# EuclideanSequencer.net
KiCad netlist of a schematic drawn in EAGLE
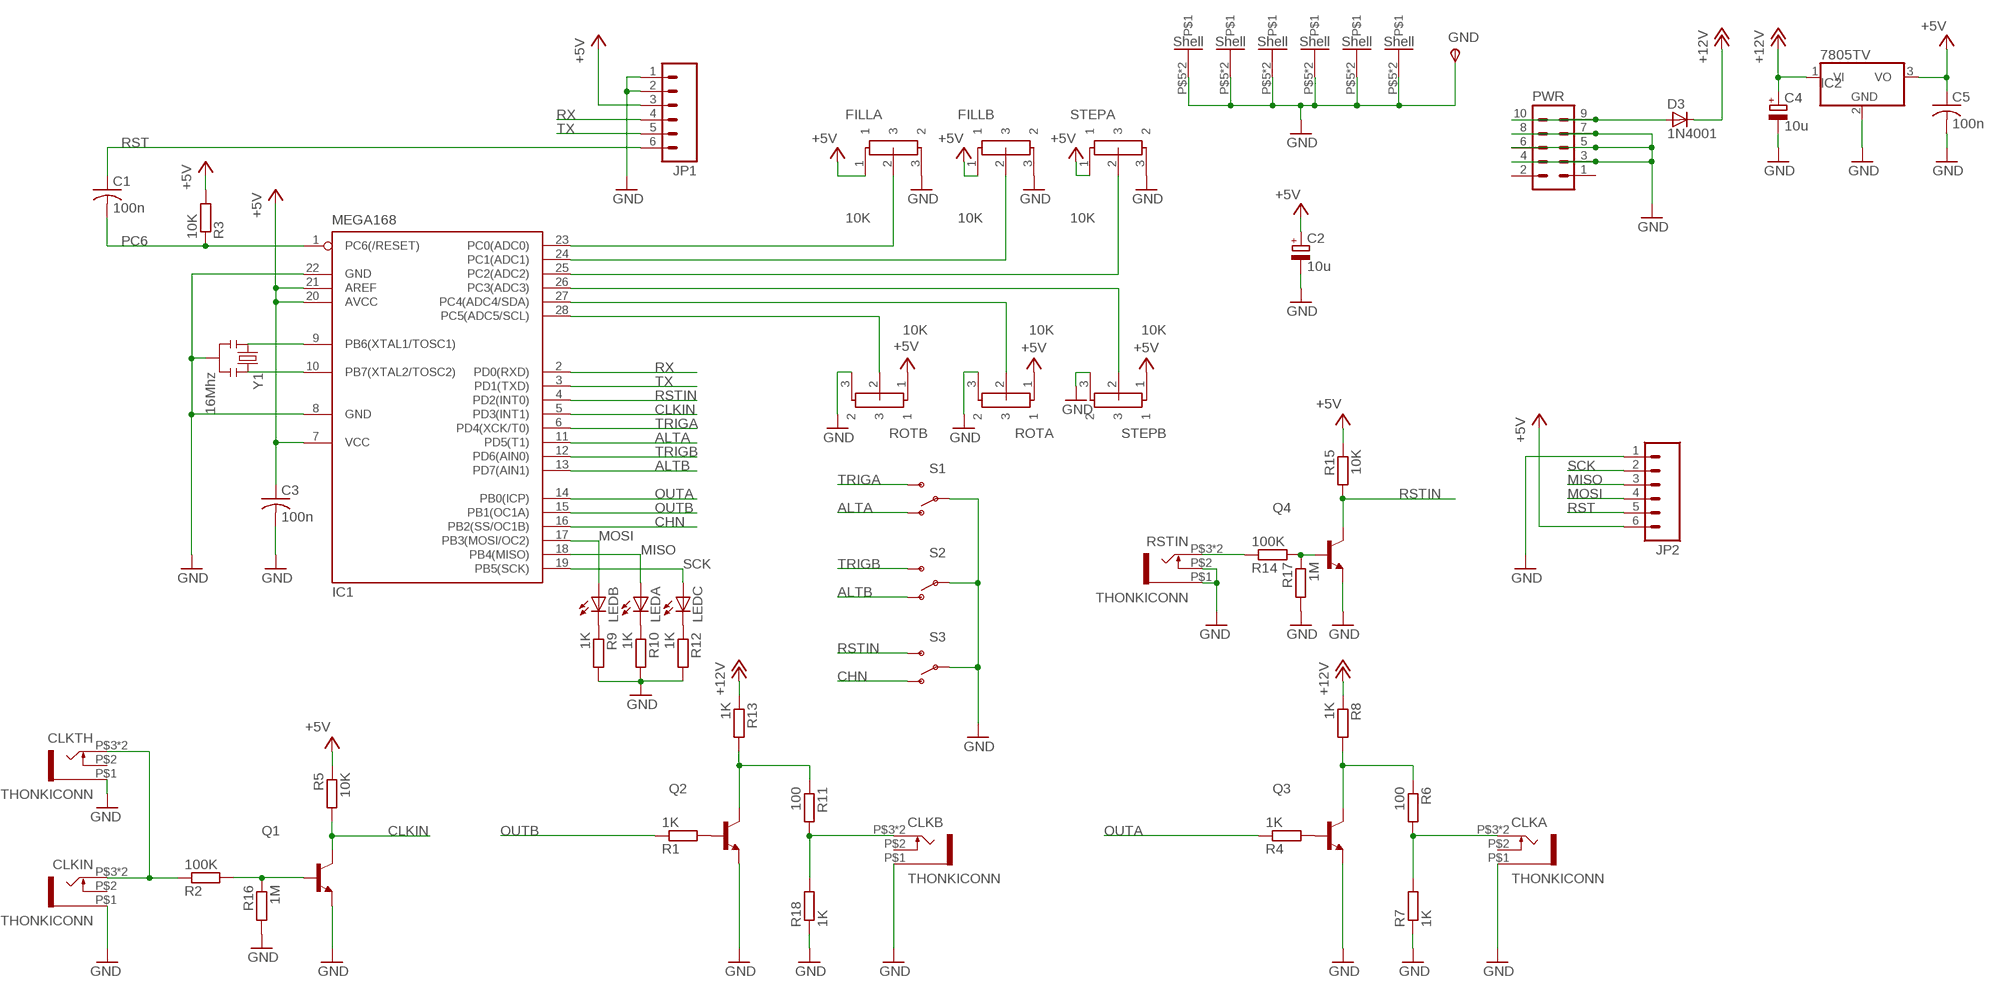
[diagram p0: schematic, sheet 1]

(export (version "E")
  (design (tool "Eeschema 10.0.6"))
  (components
    (comp (ref "C1")
      (value "100n")
      (footprint "eagle-import:C050-024X044")
      (libsource (lib "eagle-import") (part "C-US050-024X044"))
    )
    (comp (ref "C2")
      (value "10u")
      (footprint "eagle-import:E5-6")
      (libsource (lib "eagle-import") (part "CPOL-EUE5-6"))
    )
    (comp (ref "C3")
      (value "100n")
      (footprint "eagle-import:C050-024X044")
      (libsource (lib "eagle-import") (part "C-US050-024X044"))
    )
    (comp (ref "C4")
      (value "10u")
      (footprint "eagle-import:E5-6")
      (libsource (lib "eagle-import") (part "CPOL-EUE5-6"))
    )
    (comp (ref "C5")
      (value "100n")
      (footprint "eagle-import:C050-024X044")
      (libsource (lib "eagle-import") (part "C-US050-024X044"))
    )
    (comp (ref "CLKA")
      (value "THONKICONN")
      (footprint "eagle-import:THONKICONN")
      (libsource (lib "eagle-import") (part "THONKICONN"))
    )
    (comp (ref "CLKB")
      (value "THONKICONN")
      (footprint "eagle-import:THONKICONN")
      (libsource (lib "eagle-import") (part "THONKICONN"))
    )
    (comp (ref "CLKIN")
      (value "THONKICONN")
      (footprint "eagle-import:THONKICONN")
      (libsource (lib "eagle-import") (part "THONKICONN"))
    )
    (comp (ref "CLKTH")
      (value "THONKICONN")
      (footprint "eagle-import:THONKICONN")
      (libsource (lib "eagle-import") (part "THONKICONN"))
    )
    (comp (ref "D3")
      (value "1N4001")
      (footprint "eagle-import:DIODE-1N4001")
      (libsource (lib "eagle-import") (part "DIODE1N4001"))
    )
    (comp (ref "FILLA")
      (value "10K")
      (footprint "eagle-import:POT-ALPS-RK09L1140")
      (libsource (lib "eagle-import") (part "POT-ALPS_ALPS290024"))
    )
    (comp (ref "FILLB")
      (value "10K")
      (footprint "eagle-import:POT-ALPS-RK09L1140")
      (libsource (lib "eagle-import") (part "POT-ALPS_ALPS290024"))
    )
    (comp (ref "GND")
      (value "TPSPAD1-20")
      (footprint "eagle-import:P1-20")
      (libsource (lib "eagle-import") (part "TPSPAD1-20"))
    )
    (comp (ref "IC1")
      (value "MEGA168")
      (footprint "eagle-import:DIL28-3")
      (libsource (lib "eagle-import") (part "MEGA8-P"))
    )
    (comp (ref "IC2")
      (value "7805TV")
      (footprint "eagle-import:TO220V")
      (libsource (lib "eagle-import") (part "78TV05"))
    )
    (comp (ref "JP1")
      (value "M06SIP")
      (footprint "eagle-import:1X06")
      (libsource (lib "eagle-import") (part "M06SIP"))
    )
    (comp (ref "JP2")
      (value "M06SIP")
      (footprint "eagle-import:1X06")
      (libsource (lib "eagle-import") (part "M06SIP"))
    )
    (comp (ref "LEDA")
      (value "LED3MM")
      (footprint "eagle-import:LED3MM")
      (libsource (lib "eagle-import") (part "LED3MM"))
    )
    (comp (ref "LEDB")
      (value "LED3MM")
      (footprint "eagle-import:LED3MM")
      (libsource (lib "eagle-import") (part "LED3MM"))
    )
    (comp (ref "LEDC")
      (value "LED3MM")
      (footprint "eagle-import:LED3MM")
      (libsource (lib "eagle-import") (part "LED3MM"))
    )
    (comp (ref "PWR")
      (value "MA05-2")
      (footprint "eagle-import:MA05-2")
      (libsource (lib "eagle-import") (part "MA05-2"))
    )
    (comp (ref "Q1")
      (value "2N3904-NPN-TO92-EBC")
      (footprint "eagle-import:TO92-EBC")
      (libsource (lib "eagle-import") (part "-NPN-TO92-EBC2N3904"))
    )
    (comp (ref "Q2")
      (value "2N3904-NPN-TO92-EBC")
      (footprint "eagle-import:TO92-EBC")
      (libsource (lib "eagle-import") (part "-NPN-TO92-EBC2N3904"))
    )
    (comp (ref "Q3")
      (value "2N3904-NPN-TO92-EBC")
      (footprint "eagle-import:TO92-EBC")
      (libsource (lib "eagle-import") (part "-NPN-TO92-EBC2N3904"))
    )
    (comp (ref "Q4")
      (value "2N3904-NPN-TO92-EBC")
      (footprint "eagle-import:TO92-EBC")
      (libsource (lib "eagle-import") (part "-NPN-TO92-EBC2N3904"))
    )
    (comp (ref "R1")
      (value "1K")
      (footprint "eagle-import:0204_7")
      (libsource (lib "eagle-import") (part "R-EU_0204/7"))
    )
    (comp (ref "R2")
      (value "100K")
      (footprint "eagle-import:0204_7")
      (libsource (lib "eagle-import") (part "R-EU_0204/7"))
    )
    (comp (ref "R3")
      (value "10K")
      (footprint "eagle-import:0204_7")
      (libsource (lib "eagle-import") (part "R-EU_0204/7"))
    )
    (comp (ref "R4")
      (value "1K")
      (footprint "eagle-import:0204_7")
      (libsource (lib "eagle-import") (part "R-EU_0204/7"))
    )
    (comp (ref "R5")
      (value "10K")
      (footprint "eagle-import:0204_7")
      (libsource (lib "eagle-import") (part "R-EU_0204/7"))
    )
    (comp (ref "R6")
      (value "100")
      (footprint "eagle-import:0204_7")
      (libsource (lib "eagle-import") (part "R-EU_0204/7"))
    )
    (comp (ref "R7")
      (value "1K")
      (footprint "eagle-import:0204_7")
      (libsource (lib "eagle-import") (part "R-EU_0204/7"))
    )
    (comp (ref "R8")
      (value "1K")
      (footprint "eagle-import:0204_7")
      (libsource (lib "eagle-import") (part "R-EU_0204/7"))
    )
    (comp (ref "R9")
      (value "1K")
      (footprint "eagle-import:0204_7")
      (libsource (lib "eagle-import") (part "R-EU_0204/7"))
    )
    (comp (ref "R10")
      (value "1K")
      (footprint "eagle-import:0204_7")
      (libsource (lib "eagle-import") (part "R-EU_0204/7"))
    )
    (comp (ref "R11")
      (value "100")
      (footprint "eagle-import:0204_7")
      (libsource (lib "eagle-import") (part "R-EU_0204/7"))
    )
    (comp (ref "R12")
      (value "1K")
      (footprint "eagle-import:0204_7")
      (libsource (lib "eagle-import") (part "R-EU_0204/7"))
    )
    (comp (ref "R13")
      (value "1K")
      (footprint "eagle-import:0204_7")
      (libsource (lib "eagle-import") (part "R-EU_0204/7"))
    )
    (comp (ref "R14")
      (value "100K")
      (footprint "eagle-import:0204_7")
      (libsource (lib "eagle-import") (part "R-EU_0204/7"))
    )
    (comp (ref "R15")
      (value "10K")
      (footprint "eagle-import:0204_7")
      (libsource (lib "eagle-import") (part "R-EU_0204/7"))
    )
    (comp (ref "R16")
      (value "1M")
      (footprint "eagle-import:0204_7")
      (libsource (lib "eagle-import") (part "R-EU_0204/7"))
    )
    (comp (ref "R17")
      (value "1M")
      (footprint "eagle-import:0204_7")
      (libsource (lib "eagle-import") (part "R-EU_0204/7"))
    )
    (comp (ref "R18")
      (value "1K")
      (footprint "eagle-import:0204_7")
      (libsource (lib "eagle-import") (part "R-EU_0204/7"))
    )
    (comp (ref "ROTA")
      (value "10K")
      (footprint "eagle-import:POT-ALPS-RK09L1140")
      (libsource (lib "eagle-import") (part "POT-ALPS_ALPS290024"))
    )
    (comp (ref "ROTB")
      (value "10K")
      (footprint "eagle-import:POT-ALPS-RK09L1140")
      (libsource (lib "eagle-import") (part "POT-ALPS_ALPS290024"))
    )
    (comp (ref "RSTIN")
      (value "THONKICONN")
      (footprint "eagle-import:THONKICONN")
      (libsource (lib "eagle-import") (part "THONKICONN"))
    )
    (comp (ref "S1")
      (value "SWITCH-SPST")
      (footprint "eagle-import:SWITCH-SPDT-SALECOM-T8014")
      (libsource (lib "eagle-import") (part "SWITCH-SPST"))
    )
    (comp (ref "S2")
      (value "SWITCH-SPST")
      (footprint "eagle-import:SWITCH-SPDT-SALECOM-T8014")
      (libsource (lib "eagle-import") (part "SWITCH-SPST"))
    )
    (comp (ref "S3")
      (value "SWITCH-SPST")
      (footprint "eagle-import:SWITCH-SPDT-SALECOM-T8014")
      (libsource (lib "eagle-import") (part "SWITCH-SPST"))
    )
    (comp (ref "STEPA")
      (value "10K")
      (footprint "eagle-import:POT-ALPS-RK09L1140")
      (libsource (lib "eagle-import") (part "POT-ALPS_ALPS290024"))
    )
    (comp (ref "STEPB")
      (value "10K")
      (footprint "eagle-import:POT-ALPS-RK09L1140")
      (libsource (lib "eagle-import") (part "POT-ALPS_ALPS290024"))
    )
    (comp (ref "Y1")
      (value "16Mhz")
      (footprint "eagle-import:RESONATOR-PTH")
      (libsource (lib "eagle-import") (part "RESONATORPTH"))
    )
  )
  (nets
    (net (code "1") (name "+5V") (class "Default")
      (node (ref "C2") (pin "+") (pinfunction "+_+") (pintype "passive"))
      (node (ref "C3") (pin "1") (pinfunction "1_1") (pintype "passive"))
      (node (ref "C5") (pin "1") (pinfunction "1_1") (pintype "passive"))
      (node (ref "FILLA") (pin "1") (pinfunction "1_1") (pintype "bidirectional"))
      (node (ref "FILLB") (pin "1") (pinfunction "1_1") (pintype "bidirectional"))
      (node (ref "IC1") (pin "20") (pinfunction "AVCC_20") (pintype "power_in"))
      (node (ref "IC1") (pin "21") (pinfunction "AREF_21") (pintype "passive"))
      (node (ref "IC1") (pin "7") (pinfunction "VCC_7") (pintype "power_in"))
      (node (ref "IC2") (pin "3") (pinfunction "VO_3") (pintype "passive"))
      (node (ref "JP1") (pin "3") (pinfunction "3_3") (pintype "passive"))
      (node (ref "JP2") (pin "6") (pinfunction "6_6") (pintype "passive"))
      (node (ref "R15") (pin "1") (pinfunction "1_1") (pintype "passive"))
      (node (ref "R3") (pin "2") (pinfunction "2_2") (pintype "passive"))
      (node (ref "R5") (pin "1") (pinfunction "1_1") (pintype "passive"))
      (node (ref "ROTA") (pin "1") (pinfunction "1_1") (pintype "bidirectional"))
      (node (ref "ROTB") (pin "1") (pinfunction "1_1") (pintype "bidirectional"))
      (node (ref "STEPA") (pin "1") (pinfunction "1_1") (pintype "bidirectional"))
      (node (ref "STEPB") (pin "1") (pinfunction "1_1") (pintype "bidirectional"))
    )
    (net (code "2") (name "+12V") (class "Default")
      (node (ref "C4") (pin "+") (pinfunction "+_+") (pintype "passive"))
      (node (ref "D3") (pin "C") (pinfunction "C_C") (pintype "passive"))
      (node (ref "IC2") (pin "1") (pinfunction "VI_1") (pintype "input"))
      (node (ref "R13") (pin "1") (pinfunction "1_1") (pintype "passive"))
      (node (ref "R8") (pin "1") (pinfunction "1_1") (pintype "passive"))
    )
    (net (code "3") (name "/ALTA") (class "Default")
      (node (ref "IC1") (pin "11") (pinfunction "PD5(T1)_11") (pintype "bidirectional"))
      (node (ref "S1") (pin "1") (pinfunction "O_1") (pintype "passive"))
    )
    (net (code "4") (name "/ALTB") (class "Default")
      (node (ref "IC1") (pin "13") (pinfunction "PD7(AIN1)_13") (pintype "bidirectional"))
      (node (ref "S2") (pin "1") (pinfunction "O_1") (pintype "passive"))
    )
    (net (code "5") (name "/CHN") (class "Default")
      (node (ref "IC1") (pin "16") (pinfunction "PB2(SS/OC1B)_16") (pintype "bidirectional"))
      (node (ref "S3") (pin "1") (pinfunction "O_1") (pintype "passive"))
    )
    (net (code "6") (name "/CLKIN") (class "Default")
      (node (ref "IC1") (pin "5") (pinfunction "PD3(INT1)_5") (pintype "bidirectional"))
      (node (ref "Q1") (pin "C") (pinfunction "C_C") (pintype "passive"))
      (node (ref "R5") (pin "2") (pinfunction "2_2") (pintype "passive"))
    )
    (net (code "7") (name "/MISO") (class "Default")
      (node (ref "IC1") (pin "18") (pinfunction "PB4(MISO)_18") (pintype "bidirectional"))
      (node (ref "JP2") (pin "3") (pinfunction "3_3") (pintype "passive"))
      (node (ref "LEDA") (pin "A") (pinfunction "A_A") (pintype "passive"))
    )
    (net (code "8") (name "/MOSI") (class "Default")
      (node (ref "IC1") (pin "17") (pinfunction "PB3(MOSI/OC2)_17") (pintype "bidirectional"))
      (node (ref "JP2") (pin "4") (pinfunction "4_4") (pintype "passive"))
      (node (ref "LEDB") (pin "A") (pinfunction "A_A") (pintype "passive"))
    )
    (net (code "9") (name "/OUTA") (class "Default")
      (node (ref "IC1") (pin "14") (pinfunction "PB0(ICP)_14") (pintype "bidirectional"))
      (node (ref "R4") (pin "1") (pinfunction "1_1") (pintype "passive"))
    )
    (net (code "10") (name "/OUTB") (class "Default")
      (node (ref "IC1") (pin "15") (pinfunction "PB1(OC1A)_15") (pintype "bidirectional"))
      (node (ref "R1") (pin "1") (pinfunction "1_1") (pintype "passive"))
    )
    (net (code "11") (name "/PC6") (class "Default")
      (node (ref "C1") (pin "2") (pinfunction "2_2") (pintype "passive"))
      (node (ref "IC1") (pin "1") (pinfunction "PC6(/RESET)_1") (pintype "bidirectional"))
      (node (ref "R3") (pin "1") (pinfunction "1_1") (pintype "passive"))
    )
    (net (code "12") (name "/RST") (class "Default")
      (node (ref "C1") (pin "1") (pinfunction "1_1") (pintype "passive"))
      (node (ref "JP1") (pin "6") (pinfunction "6_6") (pintype "passive"))
      (node (ref "JP2") (pin "5") (pinfunction "5_5") (pintype "passive"))
    )
    (net (code "13") (name "/RSTIN") (class "Default")
      (node (ref "IC1") (pin "4") (pinfunction "PD2(INT0)_4") (pintype "bidirectional"))
      (node (ref "Q4") (pin "C") (pinfunction "C_C") (pintype "passive"))
      (node (ref "R15") (pin "2") (pinfunction "2_2") (pintype "passive"))
      (node (ref "S3") (pin "3") (pinfunction "S_3") (pintype "passive"))
    )
    (net (code "14") (name "/RX") (class "Default")
      (node (ref "IC1") (pin "2") (pinfunction "PD0(RXD)_2") (pintype "bidirectional"))
      (node (ref "JP1") (pin "4") (pinfunction "4_4") (pintype "passive"))
    )
    (net (code "15") (name "/SCK") (class "Default")
      (node (ref "IC1") (pin "19") (pinfunction "PB5(SCK)_19") (pintype "bidirectional"))
      (node (ref "JP2") (pin "2") (pinfunction "2_2") (pintype "passive"))
      (node (ref "LEDC") (pin "A") (pinfunction "A_A") (pintype "passive"))
    )
    (net (code "16") (name "/TRIGA") (class "Default")
      (node (ref "IC1") (pin "6") (pinfunction "PD4(XCK/T0)_6") (pintype "bidirectional"))
      (node (ref "S1") (pin "3") (pinfunction "S_3") (pintype "passive"))
    )
    (net (code "17") (name "/TRIGB") (class "Default")
      (node (ref "IC1") (pin "12") (pinfunction "PD6(AIN0)_12") (pintype "bidirectional"))
      (node (ref "S2") (pin "3") (pinfunction "S_3") (pintype "passive"))
    )
    (net (code "18") (name "/TX") (class "Default")
      (node (ref "IC1") (pin "3") (pinfunction "PD1(TXD)_3") (pintype "bidirectional"))
      (node (ref "JP1") (pin "5") (pinfunction "5_5") (pintype "passive"))
    )
    (net (code "19") (name "GND") (class "Default")
      (node (ref "C2") (pin "-") (pinfunction "-_-") (pintype "passive"))
      (node (ref "C3") (pin "2") (pinfunction "2_2") (pintype "passive"))
      (node (ref "C4") (pin "-") (pinfunction "-_-") (pintype "passive"))
      (node (ref "C5") (pin "2") (pinfunction "2_2") (pintype "passive"))
      (node (ref "CLKA") (pin "P$1") (pinfunction "5_P$1") (pintype "passive"))
      (node (ref "CLKB") (pin "P$1") (pinfunction "5_P$1") (pintype "passive"))
      (node (ref "CLKIN") (pin "P$1") (pinfunction "5_P$1") (pintype "passive"))
      (node (ref "CLKTH") (pin "P$1") (pinfunction "5_P$1") (pintype "passive"))
      (node (ref "FILLA") (pin "3") (pinfunction "2_3") (pintype "bidirectional"))
      (node (ref "FILLA") (pin "P$5") (pinfunction "P$1_P$5") (pintype "bidirectional"))
      (node (ref "FILLA") (pin "P$6") (pinfunction "P$1_P$6") (pintype "bidirectional"))
      (node (ref "FILLB") (pin "3") (pinfunction "2_3") (pintype "bidirectional"))
      (node (ref "FILLB") (pin "P$5") (pinfunction "P$1_P$5") (pintype "bidirectional"))
      (node (ref "FILLB") (pin "P$6") (pinfunction "P$1_P$6") (pintype "bidirectional"))
      (node (ref "GND") (pin "TP") (pinfunction "PP_TP") (pintype "input"))
      (node (ref "IC1") (pin "22") (pinfunction "GND_22") (pintype "power_in"))
      (node (ref "IC1") (pin "8") (pinfunction "GND_8") (pintype "power_in"))
      (node (ref "IC2") (pin "2") (pinfunction "GND_2") (pintype "passive"))
      (node (ref "JP1") (pin "1") (pinfunction "1_1") (pintype "passive"))
      (node (ref "JP1") (pin "2") (pinfunction "2_2") (pintype "passive"))
      (node (ref "JP2") (pin "1") (pinfunction "1_1") (pintype "passive"))
      (node (ref "PWR") (pin "3") (pinfunction "3_3") (pintype "passive"))
      (node (ref "PWR") (pin "4") (pinfunction "4_4") (pintype "passive"))
      (node (ref "PWR") (pin "5") (pinfunction "5_5") (pintype "passive"))
      (node (ref "PWR") (pin "6") (pinfunction "6_6") (pintype "passive"))
      (node (ref "PWR") (pin "7") (pinfunction "7_7") (pintype "passive"))
      (node (ref "PWR") (pin "8") (pinfunction "8_8") (pintype "passive"))
      (node (ref "Q1") (pin "E") (pinfunction "E_E") (pintype "passive"))
      (node (ref "Q2") (pin "E") (pinfunction "E_E") (pintype "passive"))
      (node (ref "Q3") (pin "E") (pinfunction "E_E") (pintype "passive"))
      (node (ref "Q4") (pin "E") (pinfunction "E_E") (pintype "passive"))
      (node (ref "R10") (pin "2") (pinfunction "2_2") (pintype "passive"))
      (node (ref "R12") (pin "2") (pinfunction "2_2") (pintype "passive"))
      (node (ref "R16") (pin "2") (pinfunction "2_2") (pintype "passive"))
      (node (ref "R17") (pin "2") (pinfunction "2_2") (pintype "passive"))
      (node (ref "R18") (pin "1") (pinfunction "1_1") (pintype "passive"))
      (node (ref "R7") (pin "1") (pinfunction "1_1") (pintype "passive"))
      (node (ref "R9") (pin "2") (pinfunction "2_2") (pintype "passive"))
      (node (ref "ROTA") (pin "3") (pinfunction "2_3") (pintype "bidirectional"))
      (node (ref "ROTA") (pin "P$5") (pinfunction "P$1_P$5") (pintype "bidirectional"))
      (node (ref "ROTA") (pin "P$6") (pinfunction "P$1_P$6") (pintype "bidirectional"))
      (node (ref "ROTB") (pin "3") (pinfunction "2_3") (pintype "bidirectional"))
      (node (ref "ROTB") (pin "P$5") (pinfunction "P$1_P$5") (pintype "bidirectional"))
      (node (ref "ROTB") (pin "P$6") (pinfunction "P$1_P$6") (pintype "bidirectional"))
      (node (ref "RSTIN") (pin "P$1") (pinfunction "5_P$1") (pintype "passive"))
      (node (ref "RSTIN") (pin "P$2") (pinfunction "4_P$2") (pintype "passive"))
      (node (ref "S1") (pin "2") (pinfunction "P_2") (pintype "passive"))
      (node (ref "S2") (pin "2") (pinfunction "P_2") (pintype "passive"))
      (node (ref "S3") (pin "2") (pinfunction "P_2") (pintype "passive"))
      (node (ref "STEPA") (pin "3") (pinfunction "2_3") (pintype "bidirectional"))
      (node (ref "STEPA") (pin "P$5") (pinfunction "P$1_P$5") (pintype "bidirectional"))
      (node (ref "STEPA") (pin "P$6") (pinfunction "P$1_P$6") (pintype "bidirectional"))
      (node (ref "STEPB") (pin "3") (pinfunction "2_3") (pintype "bidirectional"))
      (node (ref "STEPB") (pin "P$5") (pinfunction "P$1_P$5") (pintype "bidirectional"))
      (node (ref "STEPB") (pin "P$6") (pinfunction "P$1_P$6") (pintype "bidirectional"))
      (node (ref "Y1") (pin "2") (pinfunction "2_2") (pintype "passive"))
    )
    (net (code "20") (name "Net-(CLKA-3-PadP$3)") (class "Default")
      (node (ref "CLKA") (pin "P$3") (pinfunction "3_P$3") (pintype "passive"))
      (node (ref "CLKA") (pin "P$4") (pinfunction "3_P$4") (pintype "passive"))
      (node (ref "R6") (pin "2") (pinfunction "2_2") (pintype "passive"))
      (node (ref "R7") (pin "2") (pinfunction "2_2") (pintype "passive"))
    )
    (net (code "21") (name "Net-(CLKB-3-PadP$3)") (class "Default")
      (node (ref "CLKB") (pin "P$3") (pinfunction "3_P$3") (pintype "passive"))
      (node (ref "CLKB") (pin "P$4") (pinfunction "3_P$4") (pintype "passive"))
      (node (ref "R11") (pin "2") (pinfunction "2_2") (pintype "passive"))
      (node (ref "R18") (pin "2") (pinfunction "2_2") (pintype "passive"))
    )
    (net (code "22") (name "Net-(CLKIN-3-PadP$3)") (class "Default")
      (node (ref "CLKIN") (pin "P$3") (pinfunction "3_P$3") (pintype "passive"))
      (node (ref "CLKIN") (pin "P$4") (pinfunction "3_P$4") (pintype "passive"))
      (node (ref "CLKTH") (pin "P$3") (pinfunction "3_P$3") (pintype "passive"))
      (node (ref "CLKTH") (pin "P$4") (pinfunction "3_P$4") (pintype "passive"))
      (node (ref "R2") (pin "1") (pinfunction "1_1") (pintype "passive"))
    )
    (net (code "23") (name "Net-(D3-PadA)") (class "Default")
      (node (ref "D3") (pin "A") (pinfunction "A_A") (pintype "passive"))
      (node (ref "PWR") (pin "10") (pinfunction "10_10") (pintype "passive"))
      (node (ref "PWR") (pin "9") (pinfunction "9_9") (pintype "passive"))
    )
    (net (code "24") (name "Net-(FILLAA-3)") (class "Default")
      (node (ref "FILLA") (pin "2") (pinfunction "3_2") (pintype "bidirectional"))
      (node (ref "IC1") (pin "23") (pinfunction "PC0(ADC0)_23") (pintype "bidirectional"))
    )
    (net (code "25") (name "Net-(FILLBA-3)") (class "Default")
      (node (ref "FILLB") (pin "2") (pinfunction "3_2") (pintype "bidirectional"))
      (node (ref "IC1") (pin "24") (pinfunction "PC1(ADC1)_24") (pintype "bidirectional"))
    )
    (net (code "26") (name "Net-(IC1-PB6(XTAL1{slash}TOSC1))") (class "Default")
      (node (ref "IC1") (pin "9") (pinfunction "PB6(XTAL1/TOSC1)_9") (pintype "bidirectional"))
      (node (ref "Y1") (pin "1") (pinfunction "1_1") (pintype "passive"))
    )
    (net (code "27") (name "Net-(IC1-PB7(XTAL2{slash}TOSC2))") (class "Default")
      (node (ref "IC1") (pin "10") (pinfunction "PB7(XTAL2/TOSC2)_10") (pintype "bidirectional"))
      (node (ref "Y1") (pin "3") (pinfunction "3_3") (pintype "passive"))
    )
    (net (code "28") (name "Net-(IC1-PC2(ADC2))") (class "Default")
      (node (ref "IC1") (pin "25") (pinfunction "PC2(ADC2)_25") (pintype "bidirectional"))
      (node (ref "STEPA") (pin "2") (pinfunction "3_2") (pintype "bidirectional"))
    )
    (net (code "29") (name "Net-(IC1-PC3(ADC3))") (class "Default")
      (node (ref "IC1") (pin "26") (pinfunction "PC3(ADC3)_26") (pintype "bidirectional"))
      (node (ref "STEPB") (pin "2") (pinfunction "3_2") (pintype "bidirectional"))
    )
    (net (code "30") (name "Net-(IC1-PC4(ADC4{slash}SDA))") (class "Default")
      (node (ref "IC1") (pin "27") (pinfunction "PC4(ADC4/SDA)_27") (pintype "bidirectional"))
      (node (ref "ROTA") (pin "2") (pinfunction "3_2") (pintype "bidirectional"))
    )
    (net (code "31") (name "Net-(IC1-PC5(ADC5{slash}SCL))") (class "Default")
      (node (ref "IC1") (pin "28") (pinfunction "PC5(ADC5/SCL)_28") (pintype "bidirectional"))
      (node (ref "ROTB") (pin "2") (pinfunction "3_2") (pintype "bidirectional"))
    )
    (net (code "32") (name "Net-(LEDA-C)") (class "Default")
      (node (ref "LEDA") (pin "K") (pinfunction "C_K") (pintype "passive"))
      (node (ref "R10") (pin "1") (pinfunction "1_1") (pintype "passive"))
    )
    (net (code "33") (name "Net-(LEDB-C)") (class "Default")
      (node (ref "LEDB") (pin "K") (pinfunction "C_K") (pintype "passive"))
      (node (ref "R9") (pin "1") (pinfunction "1_1") (pintype "passive"))
    )
    (net (code "34") (name "Net-(LEDC-C)") (class "Default")
      (node (ref "LEDC") (pin "K") (pinfunction "C_K") (pintype "passive"))
      (node (ref "R12") (pin "1") (pinfunction "1_1") (pintype "passive"))
    )
    (net (code "35") (name "Net-(Q1-PadB)") (class "Default")
      (node (ref "Q1") (pin "B") (pinfunction "B_B") (pintype "passive"))
      (node (ref "R16") (pin "1") (pinfunction "1_1") (pintype "passive"))
      (node (ref "R2") (pin "2") (pinfunction "2_2") (pintype "passive"))
    )
    (net (code "36") (name "Net-(Q2-PadB)") (class "Default")
      (node (ref "Q2") (pin "B") (pinfunction "B_B") (pintype "passive"))
      (node (ref "R1") (pin "2") (pinfunction "2_2") (pintype "passive"))
    )
    (net (code "37") (name "Net-(Q2-PadC)") (class "Default")
      (node (ref "Q2") (pin "C") (pinfunction "C_C") (pintype "passive"))
      (node (ref "R11") (pin "1") (pinfunction "1_1") (pintype "passive"))
      (node (ref "R13") (pin "2") (pinfunction "2_2") (pintype "passive"))
    )
    (net (code "38") (name "Net-(Q3-PadB)") (class "Default")
      (node (ref "Q3") (pin "B") (pinfunction "B_B") (pintype "passive"))
      (node (ref "R4") (pin "2") (pinfunction "2_2") (pintype "passive"))
    )
    (net (code "39") (name "Net-(Q3-PadC)") (class "Default")
      (node (ref "Q3") (pin "C") (pinfunction "C_C") (pintype "passive"))
      (node (ref "R6") (pin "1") (pinfunction "1_1") (pintype "passive"))
      (node (ref "R8") (pin "2") (pinfunction "2_2") (pintype "passive"))
    )
    (net (code "40") (name "Net-(Q4-PadB)") (class "Default")
      (node (ref "Q4") (pin "B") (pinfunction "B_B") (pintype "passive"))
      (node (ref "R14") (pin "2") (pinfunction "2_2") (pintype "passive"))
      (node (ref "R17") (pin "1") (pinfunction "1_1") (pintype "passive"))
    )
    (net (code "41") (name "Net-(R14-Pad1)") (class "Default")
      (node (ref "R14") (pin "1") (pinfunction "1_1") (pintype "passive"))
      (node (ref "RSTIN") (pin "P$3") (pinfunction "3_P$3") (pintype "passive"))
      (node (ref "RSTIN") (pin "P$4") (pinfunction "3_P$4") (pintype "passive"))
    )
    (net (code "42") (name "unconnected-(CLKA-4-PadP$2)") (class "Default")
      (node (ref "CLKA") (pin "P$2") (pinfunction "4_P$2") (pintype "passive"))
    )
    (net (code "43") (name "unconnected-(CLKB-4-PadP$2)") (class "Default")
      (node (ref "CLKB") (pin "P$2") (pinfunction "4_P$2") (pintype "passive"))
    )
    (net (code "44") (name "unconnected-(CLKIN-4-PadP$2)") (class "Default")
      (node (ref "CLKIN") (pin "P$2") (pinfunction "4_P$2") (pintype "passive"))
    )
    (net (code "45") (name "unconnected-(CLKTH-4-PadP$2)") (class "Default")
      (node (ref "CLKTH") (pin "P$2") (pinfunction "4_P$2") (pintype "passive"))
    )
    (net (code "46") (name "unconnected-(PWR-Pad1)") (class "Default")
      (node (ref "PWR") (pin "1") (pinfunction "1_1") (pintype "passive"))
    )
    (net (code "47") (name "unconnected-(PWR-Pad2)") (class "Default")
      (node (ref "PWR") (pin "2") (pinfunction "2_2") (pintype "passive"))
    )
  )
)
